# VREG_RT9166-28PVL_with_EN.net
KiCad netlist of a schematic drawn in Altium Designer
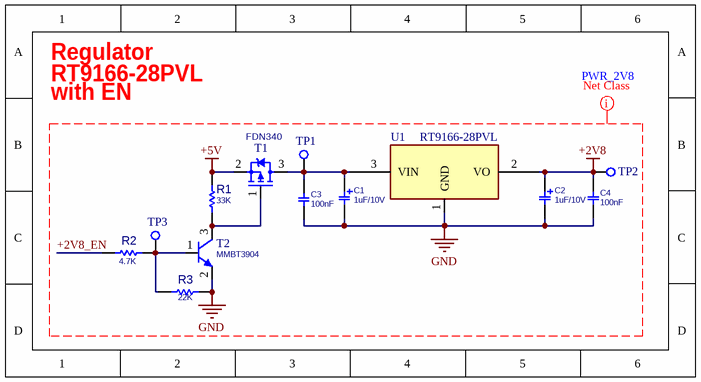
[diagram p0: VREG RT9166-28PVL with EN.SchDoc]

(export (version "E")
  (design (tool "Eeschema 10.0.6"))
  (components
    (comp (ref "C1")
      (value "1uF/10V")
      (footprint "C_TN_A")
      (description "CAP, SMD, TAN")
      (libsource (lib "PW Components 97_492") (part "CAP_SMD_TAN"))
    )
    (comp (ref "C2")
      (value "1uF/10V")
      (footprint "C_TN_A")
      (description "CAP, SMD, TAN")
      (libsource (lib "PW Components 97_492") (part "CAP_SMD_TAN"))
    )
    (comp (ref "C3")
      (value "100nF")
      (footprint "C0603S")
      (description "CAP, SMD, MLCC")
      (fields (field (name "MANF_P#") "MANF_PART#") (field (name "MANF") "Murata"))
      (libsource (lib "Passive") (part "CAP_SMD_MLCC"))
    )
    (comp (ref "C4")
      (value "100nF")
      (footprint "C0603S")
      (description "CAP, SMD, MLCC")
      (fields (field (name "MANF_P#") "MANF_PART#") (field (name "MANF") "Murata"))
      (libsource (lib "Passive") (part "CAP_SMD_MLCC"))
    )
    (comp (ref "R1")
      (value "33K")
      (footprint "R0603S")
      (description "RES, SMD")
      (fields (field (name "MANF_P#") "RK73H1ETTP4701F") (field (name "MANF") "KOA SPEER"))
      (libsource (lib "Passive") (part "RES_SMD"))
    )
    (comp (ref "R2")
      (value "4.7K")
      (footprint "R0603S")
      (description "RES, SMD")
      (fields (field (name "MANF_P#") "RK73H1ETTP4701F") (field (name "MANF") "KOA SPEER"))
      (libsource (lib "Passive") (part "RES_SMD"))
    )
    (comp (ref "R3")
      (value "22K")
      (footprint "R0603S")
      (description "RES, SMD")
      (fields (field (name "MANF_P#") "RK73H1ETTP4701F") (field (name "MANF") "KOA SPEER"))
      (libsource (lib "Passive") (part "RES_SMD"))
    )
    (comp (ref "T1")
      (value "FDN340")
      (footprint "SOT23_3")
      (description "MOSFET SMD P-CH 20V 2A")
      (fields (field (name "MANF_P#") "FDN360"))
      (libsource (lib "Transistor FET") (part "MOSP_FDN340_SOT23"))
    )
    (comp (ref "T2")
      (value "MMBT3904")
      (footprint "SOT23_3")
      (description "BJT, NPN, 40V, 0.2A, SMD, SOT23")
      (fields (field (name "MANF") "Diodes, NXP, FAIRCHILD, ON"))
      (libsource (lib "Transistor BJT") (part "NPN_MMBT3904_SOT23"))
    )
    (comp (ref "TP1")
      (value "Test Point")
      (footprint "TPSMD_C1")
      (libsource (lib "Passives") (part "Test Point"))
    )
    (comp (ref "TP2")
      (value "Test Point")
      (footprint "TPSMD_C1")
      (libsource (lib "Passives") (part "Test Point"))
    )
    (comp (ref "TP3")
      (value "Test Point")
      (footprint "TPSMD_C1")
      (libsource (lib "Passives") (part "Test Point"))
    )
    (comp (ref "U1")
      (value "RT9166-28PVL")
      (footprint "SOT23_3")
      (description "REG, Linear, Fixed, 2.8v, 0.3A/0.6A, SOT23")
      (fields (field (name "MANF") "TI"))
      (libsource (lib "PW Components 97_481") (part "VREG_RT9166A-28PVL_SOT23"))
    )
  )
  (nets
    (net (code "1") (name "+2V8") (class "Default")
      (node (ref "C2") (pin "1") (pinfunction "1_1") (pintype "passive"))
      (node (ref "C4") (pin "1") (pinfunction "1_1") (pintype "passive"))
      (node (ref "TP2") (pin "1") (pinfunction "TP_1") (pintype "passive"))
      (node (ref "U1") (pin "2") (pinfunction "VO_2") (pintype "passive"))
    )
    (net (code "2") (name "+5V") (class "Default")
      (node (ref "R1") (pin "2") (pinfunction "2_2") (pintype "passive"))
      (node (ref "T1") (pin "2") (pinfunction "S_2") (pintype "passive"))
    )
    (net (code "3") (name "/+2V8_EN") (class "Default")
      (node (ref "R2") (pin "2") (pinfunction "2_2") (pintype "passive"))
    )
    (net (code "4") (name "GND") (class "Default")
      (node (ref "C1") (pin "2") (pinfunction "2_2") (pintype "passive"))
      (node (ref "C2") (pin "2") (pinfunction "2_2") (pintype "passive"))
      (node (ref "C3") (pin "2") (pinfunction "2_2") (pintype "passive"))
      (node (ref "C4") (pin "2") (pinfunction "2_2") (pintype "passive"))
      (node (ref "R3") (pin "1") (pinfunction "1_1") (pintype "passive"))
      (node (ref "T2") (pin "2") (pinfunction "E_2") (pintype "passive"))
      (node (ref "U1") (pin "1") (pinfunction "GND_1") (pintype "passive"))
    )
    (net (code "5") (name "Net-(T1-D)") (class "Default")
      (node (ref "C1") (pin "1") (pinfunction "1_1") (pintype "passive"))
      (node (ref "C3") (pin "1") (pinfunction "1_1") (pintype "passive"))
      (node (ref "T1") (pin "3") (pinfunction "D_3") (pintype "passive"))
      (node (ref "TP1") (pin "1") (pinfunction "TP_1") (pintype "passive"))
      (node (ref "U1") (pin "3") (pinfunction "VIN_3") (pintype "passive"))
    )
    (net (code "6") (name "Net-(T1-G)") (class "Default")
      (node (ref "R1") (pin "1") (pinfunction "1_1") (pintype "passive"))
      (node (ref "T1") (pin "1") (pinfunction "G_1") (pintype "passive"))
      (node (ref "T2") (pin "3") (pinfunction "C_3") (pintype "passive"))
    )
    (net (code "7") (name "Net-(T2-B)") (class "Default")
      (node (ref "R2") (pin "1") (pinfunction "1_1") (pintype "passive"))
      (node (ref "R3") (pin "2") (pinfunction "2_2") (pintype "passive"))
      (node (ref "T2") (pin "1") (pinfunction "B_1") (pintype "passive"))
      (node (ref "TP3") (pin "1") (pinfunction "TP_1") (pintype "passive"))
    )
  )
)
